# Mach_nguon.net
KiCad netlist of a schematic drawn in Altium Designer
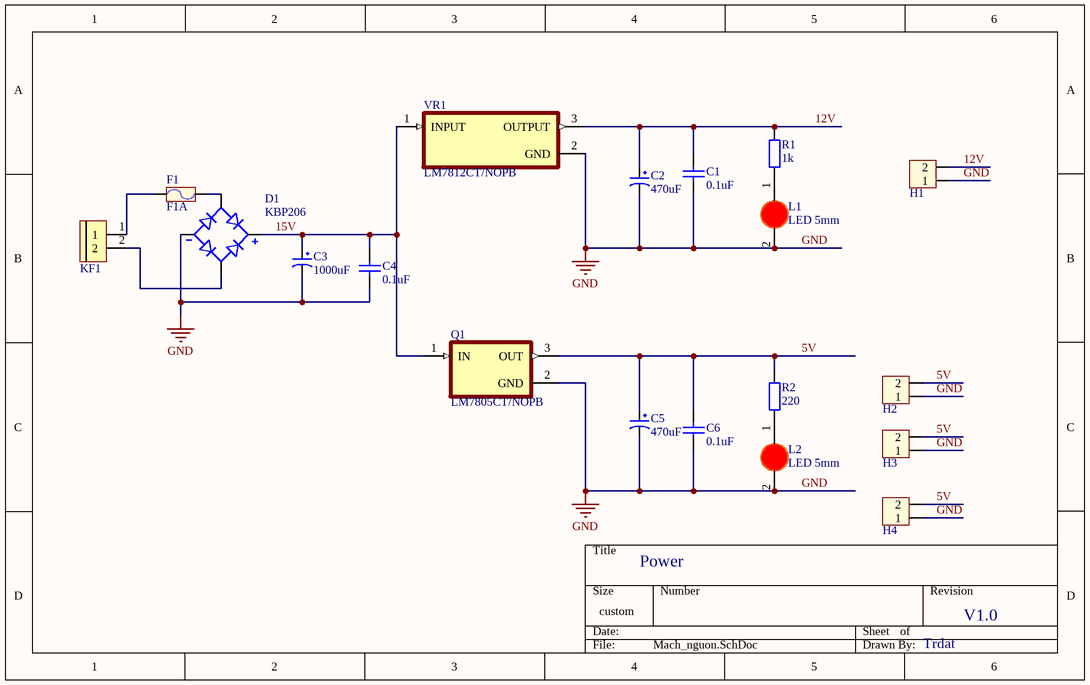
[diagram p0: Mach_nguon.SchDoc]

(export (version "E")
  (design (tool "Eeschema 10.0.6"))
  (components
    (comp (ref "C1")
      (value "0.1uF")
      (footprint "tu gom")
      (description "Cắm")
      (libsource (lib "Altium_Lib_by_KhueNguyenCreator") (part "Tu gom 100 50V"))
    )
    (comp (ref "C2")
      (value "470uF")
      (footprint "tu hoa 8mm")
      (description "Cắm")
      (libsource (lib "Altium_Lib_by_KhueNguyenCreator") (part "Tu Hoa 470uF 16V 8x11"))
    )
    (comp (ref "C3")
      (value "1000uF")
      (footprint "tu hoa 8mm")
      (description "Cắm")
      (libsource (lib "Altium_Lib_by_KhueNguyenCreator") (part "Tu Hoa 1000uF 16V 8x20"))
    )
    (comp (ref "C4")
      (value "0.1uF")
      (footprint "tu gom")
      (description "Cắm")
      (libsource (lib "Altium_Lib_by_KhueNguyenCreator") (part "Tu gom 100 50V"))
    )
    (comp (ref "C5")
      (value "470uF")
      (footprint "tu hoa 8mm")
      (description "Cắm")
      (libsource (lib "Altium_Lib_by_KhueNguyenCreator") (part "Tu Hoa 470uF 16V 8x11"))
    )
    (comp (ref "C6")
      (value "0.1uF")
      (footprint "tu gom")
      (description "Cắm")
      (libsource (lib "Altium_Lib_by_KhueNguyenCreator") (part "Tu gom 100 50V"))
    )
    (comp (ref "D1")
      (value "KBP206")
      (footprint "SIP380W81P386L1470H1270Q4")
      (description "ÛŒÚ©Ø³Ùˆ Ú©Ù†Ù†Ø¯Ù‡ Ù¾Ù„ ØªÚ© ÙØ§Ø² Ø§Ø³ØªØ§Ù†Ø¯Ø§Ø±Ø¯ 600 ÙˆÙ„Øª Ø§Ø² Ø·Ø±ÛŒÙ‚ Ø³ÙˆØ±Ø§Ø® KBP")
      (fields (field (name "MF") "GeneSiC Semiconductor"))
      (libsource (lib "KBP206") (part "KBP206"))
    )
    (comp (ref "F1")
      (value "F1A")
      (footprint "Fuse1")
      (description "Fuse")
      (fields (field (name "DESIGNED BY") "VanDungEvn"))
      (libsource (lib "LIBRARY") (part "Fuse"))
    )
    (comp (ref "H1")
      (value "Header 2P 2.54 Duc Cong")
      (footprint "Header 2P DC 2.54")
      (description "Cắm")
      (libsource (lib "Altium_Lib_by_KhueNguyenCreator") (part "Header 2P 2.54 Duc Cong"))
    )
    (comp (ref "H2")
      (value "Header 2P 2.54 Duc Cong")
      (footprint "Header 2P DC 2.54")
      (description "Cắm")
      (libsource (lib "Altium_Lib_by_KhueNguyenCreator") (part "Header 2P 2.54 Duc Cong"))
    )
    (comp (ref "H3")
      (value "Header 2P 2.54 Duc Cong")
      (footprint "Header 2P DC 2.54")
      (description "Cắm")
      (libsource (lib "Altium_Lib_by_KhueNguyenCreator") (part "Header 2P 2.54 Duc Cong"))
    )
    (comp (ref "H4")
      (value "Header 2P 2.54 Duc Cong")
      (footprint "Header 2P DC 2.54")
      (description "Cắm")
      (libsource (lib "Altium_Lib_by_KhueNguyenCreator") (part "Header 2P 2.54 Duc Cong"))
    )
    (comp (ref "KF1")
      (value "CON 2 KF301")
      (footprint "Con 2 KF301 5.08")
      (description "Cắm")
      (libsource (lib "Altium_Lib_by_KhueNguyenCreator") (part "CON 2 KF301"))
    )
    (comp (ref "L1")
      (value "LED 5mm")
      (footprint "LED-5MM-RED")
      (description "Cắm")
      (libsource (lib "Altium_Lib_by_KhueNguyenCreator") (part "LED 5mm Do"))
    )
    (comp (ref "L2")
      (value "LED 5mm")
      (footprint "LED-5MM-RED")
      (description "Cắm")
      (libsource (lib "Altium_Lib_by_KhueNguyenCreator") (part "LED 5mm Do"))
    )
    (comp (ref "Q1")
      (value "LM7805CT/NOPB")
      (footprint "TO254P1054X470X2600-3")
      (description "Linear Voltage Regulator IC Positive Fixed 1 Output 1.5A TO-220-3")
      (fields (field (name "MF") "ON Semiconductor") (field (name "MP") "LM7805CT"))
      (libsource (lib "LM7805CT_NOPB") (part "LM7805CT/NOPB"))
    )
    (comp (ref "R1")
      (value "1k")
      (footprint "tro vach 1/2w")
      (description "Cắm")
      (libsource (lib "Altium_Lib_by_KhueNguyenCreator") (part "Tro Vach 1/2W 5% 1k"))
    )
    (comp (ref "R2")
      (value "220")
      (footprint "tro vach 1/2w")
      (description "Cắm")
      (libsource (lib "Altium_Lib_by_KhueNguyenCreator") (part "Tro Vach 1/2W 5% 1k"))
    )
    (comp (ref "VR1")
      (value "LM7812CT/NOPB")
      (footprint "TO254P1054X470X1955-3")
      (description "1.5-A, 30-V, linear voltage regulator")
      (fields (field (name "MF") "Texas Instruments"))
      (libsource (lib "LM7812CT_NOPB") (part "LM7812CT/NOPB"))
    )
  )
  (nets
    (net (code "1") (name "/5V") (class "Default")
      (node (ref "C5") (pin "1") (pinfunction "1_1") (pintype "passive"))
      (node (ref "C6") (pin "1") (pinfunction "1_1") (pintype "passive"))
      (node (ref "H2") (pin "2") (pinfunction "2_2") (pintype "passive"))
      (node (ref "H3") (pin "2") (pinfunction "2_2") (pintype "passive"))
      (node (ref "H4") (pin "2") (pinfunction "2_2") (pintype "passive"))
      (node (ref "Q1") (pin "3") (pinfunction "OUT_3") (pintype "output"))
      (node (ref "R2") (pin "2") (pinfunction "2_2") (pintype "passive"))
    )
    (net (code "2") (name "/12V") (class "Default")
      (node (ref "C1") (pin "1") (pinfunction "1_1") (pintype "passive"))
      (node (ref "C2") (pin "1") (pinfunction "1_1") (pintype "passive"))
      (node (ref "H1") (pin "2") (pinfunction "2_2") (pintype "passive"))
      (node (ref "R1") (pin "2") (pinfunction "2_2") (pintype "passive"))
      (node (ref "VR1") (pin "3") (pinfunction "OUTPUT_3") (pintype "output"))
    )
    (net (code "3") (name "/15V") (class "Default")
      (node (ref "C3") (pin "1") (pinfunction "1_1") (pintype "passive"))
      (node (ref "C4") (pin "1") (pinfunction "1_1") (pintype "passive"))
      (node (ref "D1") (pin "1") (pinfunction "POS_1") (pintype "passive"))
      (node (ref "Q1") (pin "1") (pinfunction "IN_1") (pintype "input"))
      (node (ref "VR1") (pin "1") (pinfunction "INPUT_1") (pintype "input"))
    )
    (net (code "4") (name "GND") (class "Default")
      (node (ref "C1") (pin "2") (pinfunction "2_2") (pintype "passive"))
      (node (ref "C2") (pin "2") (pinfunction "2_2") (pintype "passive"))
      (node (ref "C3") (pin "2") (pinfunction "2_2") (pintype "passive"))
      (node (ref "C4") (pin "2") (pinfunction "2_2") (pintype "passive"))
      (node (ref "C5") (pin "2") (pinfunction "2_2") (pintype "passive"))
      (node (ref "C6") (pin "2") (pinfunction "2_2") (pintype "passive"))
      (node (ref "D1") (pin "4") (pinfunction "NEG_4") (pintype "passive"))
      (node (ref "H1") (pin "1") (pinfunction "1_1") (pintype "passive"))
      (node (ref "H2") (pin "1") (pinfunction "1_1") (pintype "passive"))
      (node (ref "H3") (pin "1") (pinfunction "1_1") (pintype "passive"))
      (node (ref "H4") (pin "1") (pinfunction "1_1") (pintype "passive"))
      (node (ref "L1") (pin "2") (pinfunction "K_2") (pintype "passive"))
      (node (ref "L2") (pin "2") (pinfunction "K_2") (pintype "passive"))
      (node (ref "Q1") (pin "2") (pinfunction "GND_2") (pintype "power_in"))
      (node (ref "VR1") (pin "2") (pinfunction "GND_2") (pintype "power_in"))
    )
    (net (code "5") (name "Net-(D1-AC1)") (class "Default")
      (node (ref "D1") (pin "2") (pinfunction "AC1_2") (pintype "passive"))
      (node (ref "KF1") (pin "2") (pinfunction "2_2") (pintype "passive"))
    )
    (net (code "6") (name "Net-(D1-AC2)") (class "Default")
      (node (ref "D1") (pin "3") (pinfunction "AC2_3") (pintype "passive"))
      (node (ref "F1") (pin "2") (pinfunction "2_2") (pintype "passive"))
    )
    (net (code "7") (name "Net-(F1-Pad1)") (class "Default")
      (node (ref "F1") (pin "1") (pinfunction "1_1") (pintype "passive"))
      (node (ref "KF1") (pin "1") (pinfunction "1_1") (pintype "passive"))
    )
    (net (code "8") (name "Net-(L1-A)") (class "Default")
      (node (ref "L1") (pin "1") (pinfunction "A_1") (pintype "passive"))
      (node (ref "R1") (pin "1") (pinfunction "1_1") (pintype "passive"))
    )
    (net (code "9") (name "Net-(L2-A)") (class "Default")
      (node (ref "L2") (pin "1") (pinfunction "A_1") (pintype "passive"))
      (node (ref "R2") (pin "1") (pinfunction "1_1") (pintype "passive"))
    )
  )
)
